# adc-dac.net
KiCad netlist of a schematic drawn in EAGLE
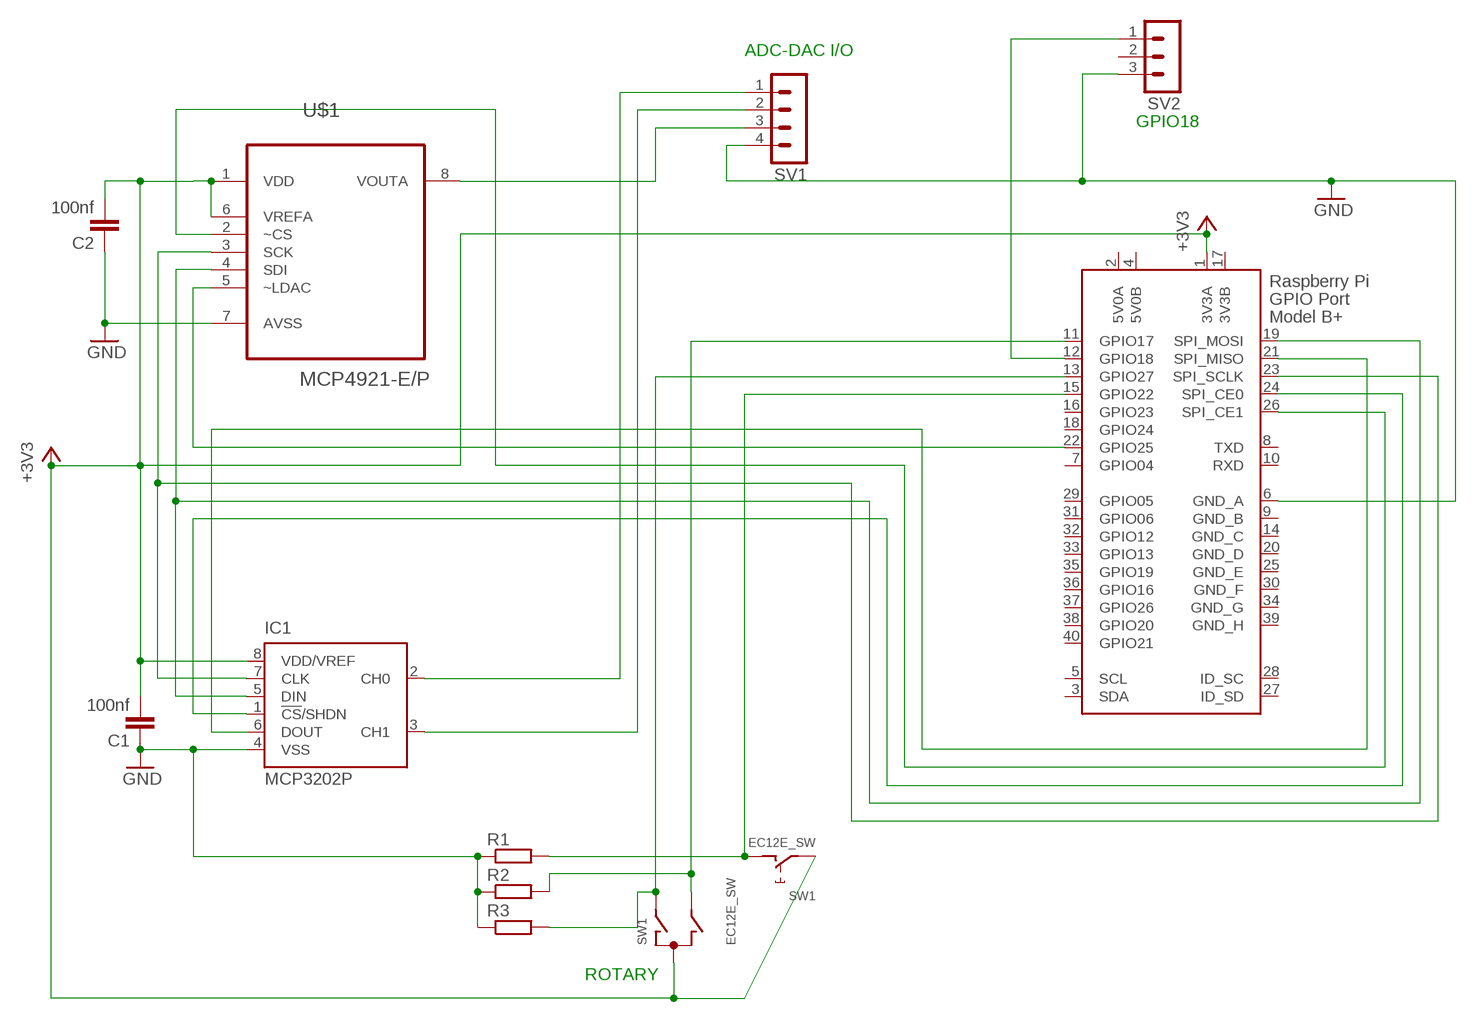
[diagram p0: schematic, sheet 1]

(export (version "E")
  (design (tool "Eeschema 10.0.6"))
  (components
    (comp (ref "C1")
      (value "100nf")
      (footprint "eagle-import:C1210")
      (libsource (lib "eagle-import") (part "C-EUC1210"))
    )
    (comp (ref "C2")
      (value "100nf")
      (footprint "eagle-import:C1210")
      (libsource (lib "eagle-import") (part "C-EUC1210"))
    )
    (comp (ref "IC1")
      (value "MCP3202P")
      (footprint "eagle-import:DIL8")
      (libsource (lib "eagle-import") (part "MCP3202P"))
    )
    (comp (ref "R1")
      (value "R-EU_0204/2V")
      (footprint "eagle-import:0204V")
      (libsource (lib "eagle-import") (part "R-EU_0204/2V"))
    )
    (comp (ref "R2")
      (value "R-EU_0204/2V")
      (footprint "eagle-import:0204V")
      (libsource (lib "eagle-import") (part "R-EU_0204/2V"))
    )
    (comp (ref "R3")
      (value "R-EU_0204/2V")
      (footprint "eagle-import:0204V")
      (libsource (lib "eagle-import") (part "R-EU_0204/2V"))
    )
    (comp (ref "SV1")
      (value "MA04-1")
      (footprint "eagle-import:MA04-1")
      (libsource (lib "eagle-import") (part "MA04-1"))
    )
    (comp (ref "SV2")
      (value "MA03-1")
      (footprint "eagle-import:MA03-1")
      (libsource (lib "eagle-import") (part "MA03-1"))
    )
    (comp (ref "SW1")
      (value "EC12E_SW")
      (footprint "eagle-import:ALPS_EC12E_SW")
      (fields (field (name "MPN") "EC12E2424407"))
      (libsource (lib "eagle-import") (part "EC12E_SW"))
    )
    (comp (ref "U$1")
      (value "MCP4921-E/P")
      (footprint "eagle-import:DIP254P762X432-8")
      (fields (field (name "MF") "Microchip"))
      (libsource (lib "eagle-import") (part "MCP4921-E/P"))
    )
    (comp (ref "X1")
      (value "RASPI_BOARD_B+#_H")
      (footprint "eagle-import:RASPI_BOARD_B+HAT")
      (libsource (lib "eagle-import") (part "RASPI_BOARD_B+#_H"))
    )
  )
  (nets
    (net (code "1") (name "+3V3") (class "Default")
      (node (ref "C1") (pin "2") (pinfunction "2_2") (pintype "passive"))
      (node (ref "C2") (pin "2") (pinfunction "2_2") (pintype "passive"))
      (node (ref "IC1") (pin "8") (pinfunction "VDD/VREF_8") (pintype "input"))
      (node (ref "SW1") (pin "C") (pinfunction "C_C") (pintype "passive"))
      (node (ref "SW1") (pin "E") (pinfunction "2_E") (pintype "passive"))
      (node (ref "U$1") (pin "1") (pinfunction "VDD_1") (pintype "power_in"))
      (node (ref "U$1") (pin "6") (pinfunction "VREFA_6") (pintype "input"))
      (node (ref "X1") (pin "1") (pinfunction "3V3A_1") (pintype "power_in"))
    )
    (net (code "2") (name "/3V3B") (class "Default")
      (node (ref "X1") (pin "17") (pinfunction "3V3B_17") (pintype "power_in"))
    )
    (net (code "3") (name "/5V0A") (class "Default")
      (node (ref "X1") (pin "2") (pinfunction "5V0A_2") (pintype "power_in"))
    )
    (net (code "4") (name "/5V0B") (class "Default")
      (node (ref "X1") (pin "4") (pinfunction "5V0B_4") (pintype "power_in"))
    )
    (net (code "5") (name "/GND_B") (class "Default")
      (node (ref "X1") (pin "9") (pinfunction "GND_B_9") (pintype "power_in"))
    )
    (net (code "6") (name "/GND_C") (class "Default")
      (node (ref "X1") (pin "14") (pinfunction "GND_C_14") (pintype "power_in"))
    )
    (net (code "7") (name "/GND_D") (class "Default")
      (node (ref "X1") (pin "20") (pinfunction "GND_D_20") (pintype "power_in"))
    )
    (net (code "8") (name "/GND_E") (class "Default")
      (node (ref "X1") (pin "25") (pinfunction "GND_E_25") (pintype "power_in"))
    )
    (net (code "9") (name "/GND_F") (class "Default")
      (node (ref "X1") (pin "30") (pinfunction "GND_F_30") (pintype "power_in"))
    )
    (net (code "10") (name "/GND_G") (class "Default")
      (node (ref "X1") (pin "34") (pinfunction "GND_G_34") (pintype "power_in"))
    )
    (net (code "11") (name "/GND_H") (class "Default")
      (node (ref "X1") (pin "39") (pinfunction "GND_H_39") (pintype "power_in"))
    )
    (net (code "12") (name "GND") (class "Default")
      (node (ref "C1") (pin "1") (pinfunction "1_1") (pintype "passive"))
      (node (ref "C2") (pin "1") (pinfunction "1_1") (pintype "passive"))
      (node (ref "IC1") (pin "4") (pinfunction "VSS_4") (pintype "input"))
      (node (ref "R1") (pin "1") (pinfunction "1_1") (pintype "passive"))
      (node (ref "R2") (pin "1") (pinfunction "1_1") (pintype "passive"))
      (node (ref "R3") (pin "1") (pinfunction "1_1") (pintype "passive"))
      (node (ref "SV1") (pin "4") (pinfunction "4_4") (pintype "passive"))
      (node (ref "SV2") (pin "3") (pinfunction "3_3") (pintype "passive"))
      (node (ref "U$1") (pin "7") (pinfunction "AVSS_7") (pintype "passive"))
      (node (ref "X1") (pin "6") (pinfunction "GND_A_6") (pintype "power_in"))
    )
    (net (code "13") (name "Net-(IC1-CH0)") (class "Default")
      (node (ref "IC1") (pin "2") (pinfunction "CH0_2") (pintype "input"))
      (node (ref "SV1") (pin "1") (pinfunction "1_1") (pintype "passive"))
    )
    (net (code "14") (name "Net-(IC1-CH1)") (class "Default")
      (node (ref "IC1") (pin "3") (pinfunction "CH1_3") (pintype "input"))
      (node (ref "SV1") (pin "2") (pinfunction "2_2") (pintype "passive"))
    )
    (net (code "15") (name "Net-(IC1-CLK)") (class "Default")
      (node (ref "IC1") (pin "7") (pinfunction "CLK_7") (pintype "input"))
      (node (ref "U$1") (pin "3") (pinfunction "SCK_3") (pintype "input"))
      (node (ref "X1") (pin "23") (pinfunction "SPI_SCLK_23") (pintype "bidirectional"))
    )
    (net (code "16") (name "Net-(IC1-DIN)") (class "Default")
      (node (ref "IC1") (pin "5") (pinfunction "DIN_5") (pintype "input"))
      (node (ref "U$1") (pin "4") (pinfunction "SDI_4") (pintype "input"))
      (node (ref "X1") (pin "19") (pinfunction "SPI_MOSI_19") (pintype "bidirectional"))
    )
    (net (code "17") (name "Net-(IC1-DOUT)") (class "Default")
      (node (ref "IC1") (pin "6") (pinfunction "DOUT_6") (pintype "input"))
      (node (ref "X1") (pin "21") (pinfunction "SPI_MISO_21") (pintype "bidirectional"))
    )
    (net (code "18") (name "Net-(IC1-~{CS}{slash}SHDN)") (class "Default")
      (node (ref "IC1") (pin "1") (pinfunction "~{CS}/SHDN_1") (pintype "input"))
      (node (ref "X1") (pin "24") (pinfunction "SPI_CE0_24") (pintype "bidirectional"))
    )
    (net (code "19") (name "Net-(SW1B-1)") (class "Default")
      (node (ref "R1") (pin "2") (pinfunction "2_2") (pintype "passive"))
      (node (ref "SW1") (pin "D") (pinfunction "1_D") (pintype "passive"))
      (node (ref "X1") (pin "15") (pinfunction "GPIO22_15") (pintype "bidirectional"))
    )
    (net (code "20") (name "Net-(U$1-VOUTA)") (class "Default")
      (node (ref "SV1") (pin "3") (pinfunction "3_3") (pintype "passive"))
      (node (ref "U$1") (pin "8") (pinfunction "VOUTA_8") (pintype "output"))
    )
    (net (code "21") (name "Net-(U$1-~{CS})") (class "Default")
      (node (ref "U$1") (pin "2") (pinfunction "~{CS}_2") (pintype "input"))
      (node (ref "X1") (pin "26") (pinfunction "SPI_CE1_26") (pintype "bidirectional"))
    )
    (net (code "22") (name "Net-(U$1-~{LDAC})") (class "Default")
      (node (ref "U$1") (pin "5") (pinfunction "~{LDAC}_5") (pintype "input"))
      (node (ref "X1") (pin "22") (pinfunction "GPIO25_22") (pintype "bidirectional"))
    )
    (net (code "23") (name "Net-(X1-GPIO17)") (class "Default")
      (node (ref "R2") (pin "2") (pinfunction "2_2") (pintype "passive"))
      (node (ref "SW1") (pin "B") (pinfunction "B_B") (pintype "passive"))
      (node (ref "X1") (pin "11") (pinfunction "GPIO17_11") (pintype "bidirectional"))
    )
    (net (code "24") (name "Net-(X1-GPIO18)") (class "Default")
      (node (ref "SV2") (pin "1") (pinfunction "1_1") (pintype "passive"))
      (node (ref "X1") (pin "12") (pinfunction "GPIO18_12") (pintype "bidirectional"))
    )
    (net (code "25") (name "Net-(X1-GPIO27)") (class "Default")
      (node (ref "R3") (pin "2") (pinfunction "2_2") (pintype "passive"))
      (node (ref "SW1") (pin "A") (pinfunction "A_A") (pintype "passive"))
      (node (ref "X1") (pin "13") (pinfunction "GPIO27_13") (pintype "bidirectional"))
    )
    (net (code "26") (name "unconnected-(SV2-Pad2)") (class "Default")
      (node (ref "SV2") (pin "2") (pinfunction "2_2") (pintype "passive"))
    )
    (net (code "27") (name "unconnected-(X1-GPIO04-Pad7)") (class "Default")
      (node (ref "X1") (pin "7") (pinfunction "GPIO04_7") (pintype "bidirectional"))
    )
    (net (code "28") (name "unconnected-(X1-GPIO05-Pad29)") (class "Default")
      (node (ref "X1") (pin "29") (pinfunction "GPIO05_29") (pintype "no_connect"))
    )
    (net (code "29") (name "unconnected-(X1-GPIO06-Pad31)") (class "Default")
      (node (ref "X1") (pin "31") (pinfunction "GPIO06_31") (pintype "no_connect"))
    )
    (net (code "30") (name "unconnected-(X1-GPIO12-Pad32)") (class "Default")
      (node (ref "X1") (pin "32") (pinfunction "GPIO12_32") (pintype "no_connect"))
    )
    (net (code "31") (name "unconnected-(X1-GPIO13-Pad33)") (class "Default")
      (node (ref "X1") (pin "33") (pinfunction "GPIO13_33") (pintype "no_connect"))
    )
    (net (code "32") (name "unconnected-(X1-GPIO16-Pad36)") (class "Default")
      (node (ref "X1") (pin "36") (pinfunction "GPIO16_36") (pintype "no_connect"))
    )
    (net (code "33") (name "unconnected-(X1-GPIO19-Pad35)") (class "Default")
      (node (ref "X1") (pin "35") (pinfunction "GPIO19_35") (pintype "no_connect"))
    )
    (net (code "34") (name "unconnected-(X1-GPIO20-Pad38)") (class "Default")
      (node (ref "X1") (pin "38") (pinfunction "GPIO20_38") (pintype "no_connect"))
    )
    (net (code "35") (name "unconnected-(X1-GPIO21-Pad40)") (class "Default")
      (node (ref "X1") (pin "40") (pinfunction "GPIO21_40") (pintype "no_connect"))
    )
    (net (code "36") (name "unconnected-(X1-GPIO23-Pad16)") (class "Default")
      (node (ref "X1") (pin "16") (pinfunction "GPIO23_16") (pintype "bidirectional"))
    )
    (net (code "37") (name "unconnected-(X1-GPIO24-Pad18)") (class "Default")
      (node (ref "X1") (pin "18") (pinfunction "GPIO24_18") (pintype "bidirectional"))
    )
    (net (code "38") (name "unconnected-(X1-GPIO26-Pad37)") (class "Default")
      (node (ref "X1") (pin "37") (pinfunction "GPIO26_37") (pintype "no_connect"))
    )
    (net (code "39") (name "unconnected-(X1-ID_SC-Pad28)") (class "Default")
      (node (ref "X1") (pin "28") (pinfunction "ID_SC_28") (pintype "no_connect"))
    )
    (net (code "40") (name "unconnected-(X1-ID_SD-Pad27)") (class "Default")
      (node (ref "X1") (pin "27") (pinfunction "ID_SD_27") (pintype "no_connect"))
    )
    (net (code "41") (name "unconnected-(X1-RXD-Pad10)") (class "Default")
      (node (ref "X1") (pin "10") (pinfunction "RXD_10") (pintype "bidirectional"))
    )
    (net (code "42") (name "unconnected-(X1-SCL-Pad5)") (class "Default")
      (node (ref "X1") (pin "5") (pinfunction "SCL_5") (pintype "bidirectional"))
    )
    (net (code "43") (name "unconnected-(X1-SDA-Pad3)") (class "Default")
      (node (ref "X1") (pin "3") (pinfunction "SDA_3") (pintype "bidirectional"))
    )
    (net (code "44") (name "unconnected-(X1-TXD-Pad8)") (class "Default")
      (node (ref "X1") (pin "8") (pinfunction "TXD_8") (pintype "bidirectional"))
    )
  )
)
